# LaserDriver.net
KiCad netlist of a schematic drawn in Altium Designer
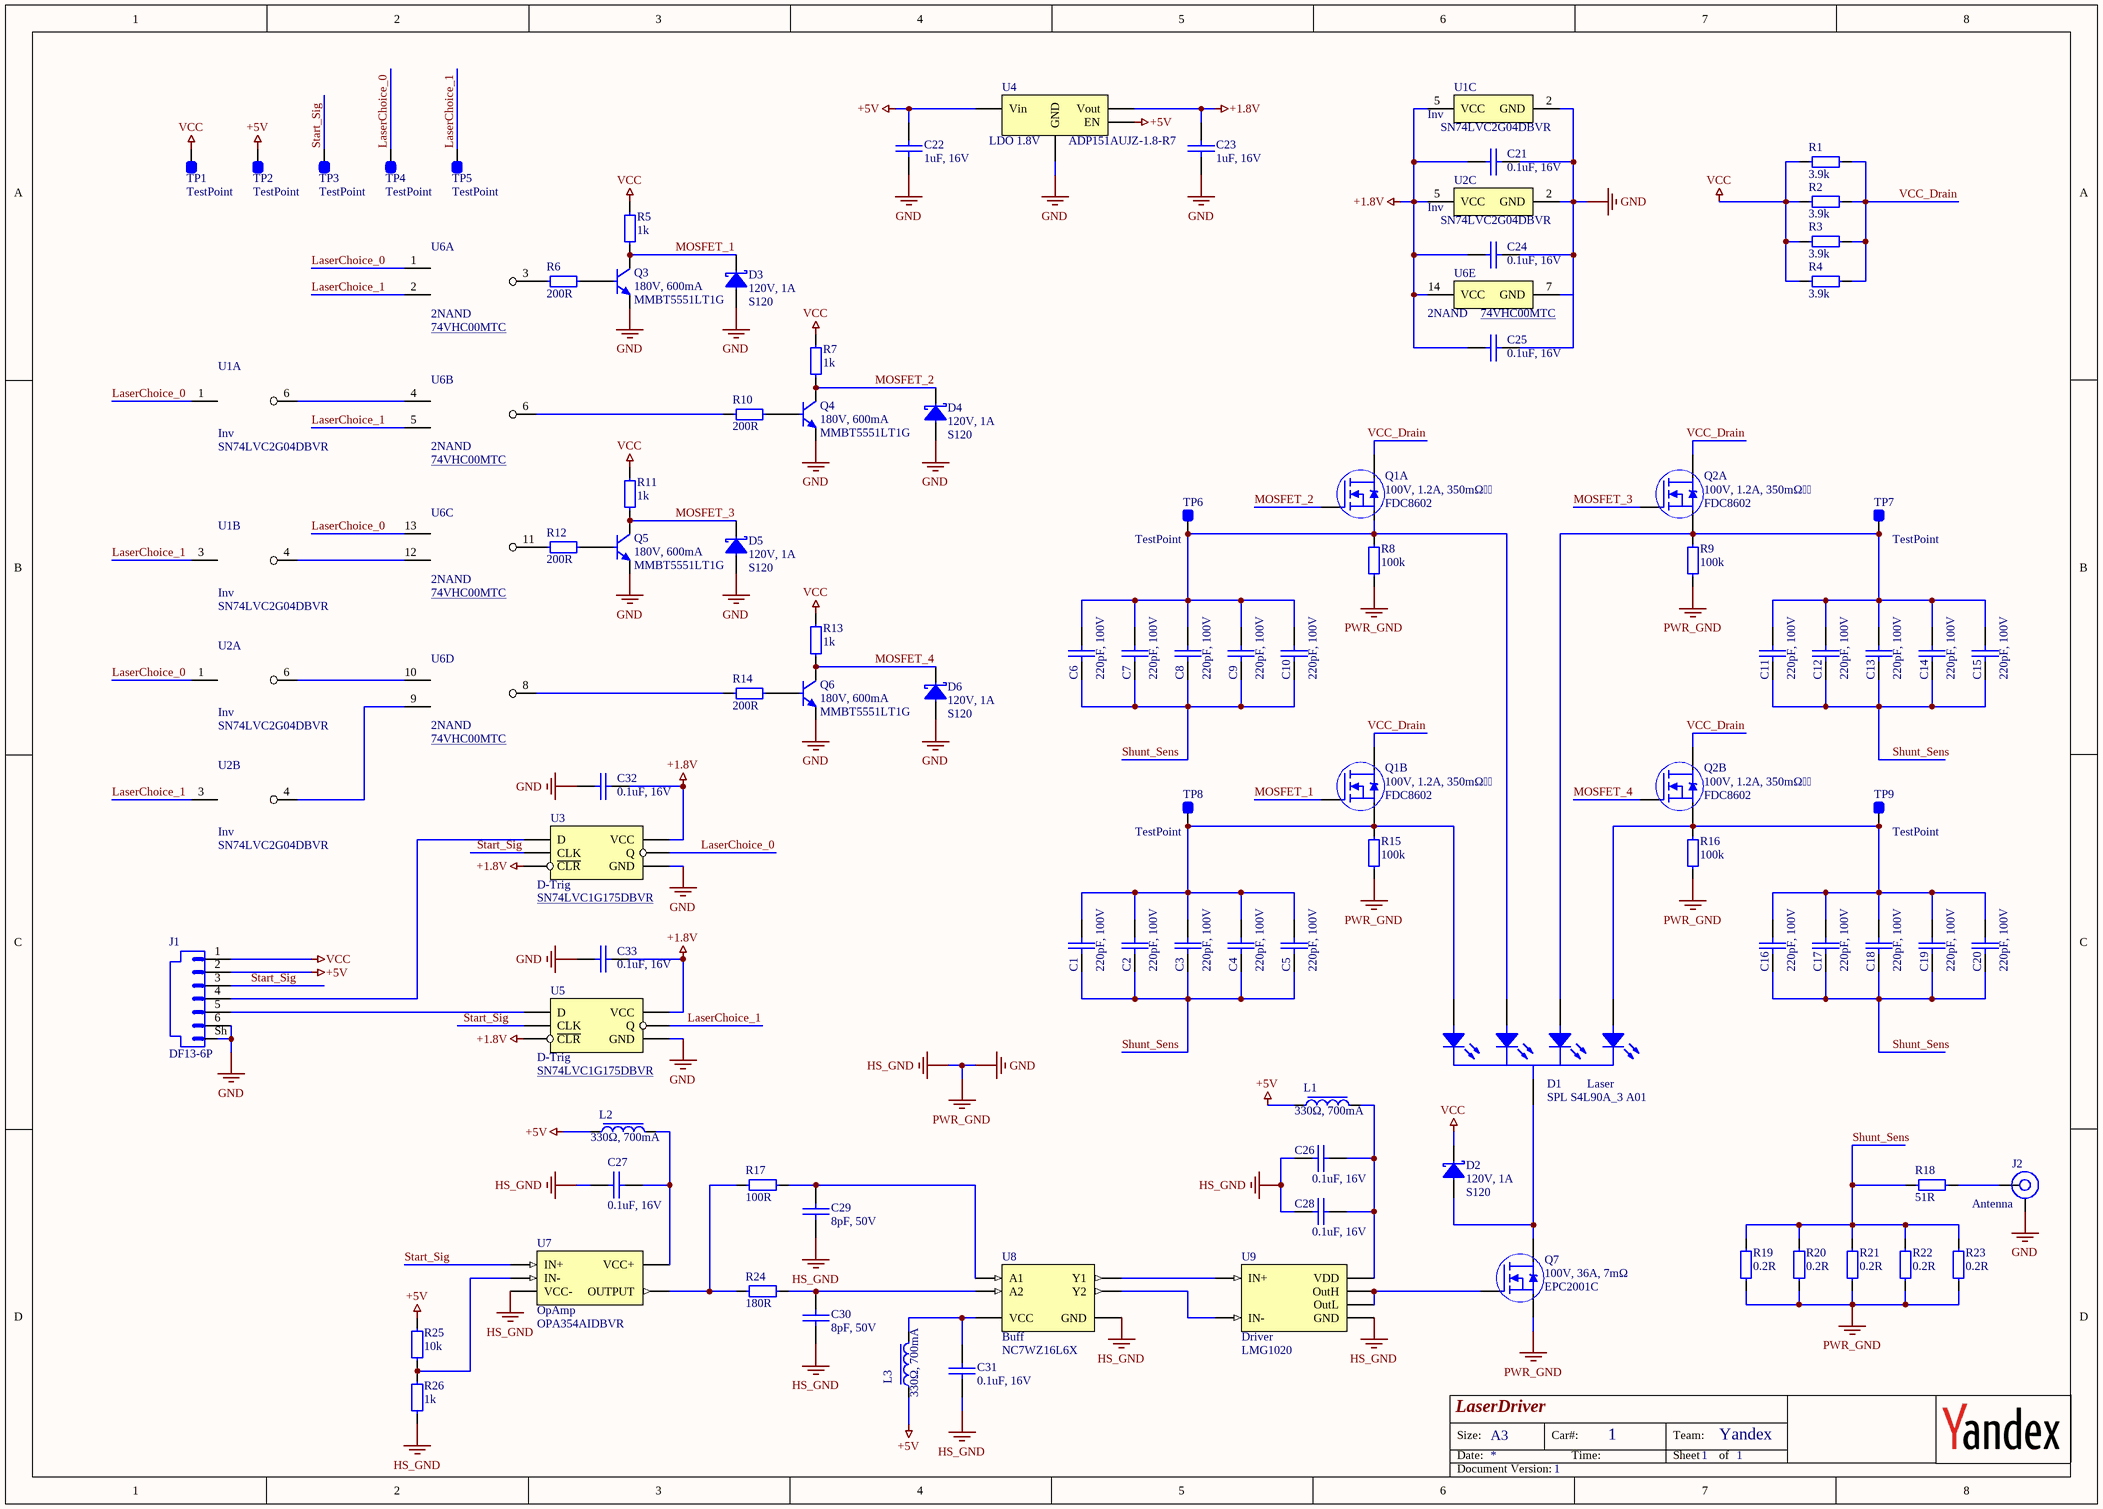
[diagram p0: LaserDriver.SchDoc]

(export (version "E")
  (design (tool "Eeschema 10.0.6"))
  (components
    (comp (ref "C1")
      (value "220pF, 100V")
      (footprint "0402 Capicator")
      (description "NP0 220pF 100V 5% 0402")
      (fields (field (name "MANUFACTURER") "TDK") (field (name "PART NUMBER") "C1005C0G2A221J050BA"))
      (libsource (lib "BRT_Components") (part "Cap 220pF (0402)"))
    )
    (comp (ref "C2")
      (value "220pF, 100V")
      (footprint "0402 Capicator")
      (description "NP0 220pF 100V 5% 0402")
      (fields (field (name "MANUFACTURER") "TDK") (field (name "PART NUMBER") "C1005C0G2A221J050BA"))
      (libsource (lib "BRT_Components") (part "Cap 220pF (0402)"))
    )
    (comp (ref "C3")
      (value "220pF, 100V")
      (footprint "0402 Capicator")
      (description "NP0 220pF 100V 5% 0402")
      (fields (field (name "MANUFACTURER") "TDK") (field (name "PART NUMBER") "C1005C0G2A221J050BA"))
      (libsource (lib "BRT_Components") (part "Cap 220pF (0402)"))
    )
    (comp (ref "C4")
      (value "220pF, 100V")
      (footprint "0402 Capicator")
      (description "NP0 220pF 100V 5% 0402")
      (fields (field (name "MANUFACTURER") "TDK") (field (name "PART NUMBER") "C1005C0G2A221J050BA"))
      (libsource (lib "BRT_Components") (part "Cap 220pF (0402)"))
    )
    (comp (ref "C5")
      (value "220pF, 100V")
      (footprint "0402 Capicator")
      (description "NP0 220pF 100V 5% 0402")
      (fields (field (name "MANUFACTURER") "TDK") (field (name "PART NUMBER") "C1005C0G2A221J050BA"))
      (libsource (lib "BRT_Components") (part "Cap 220pF (0402)"))
    )
    (comp (ref "C6")
      (value "220pF, 100V")
      (footprint "0402 Capicator")
      (description "NP0 220pF 100V 5% 0402")
      (fields (field (name "MANUFACTURER") "TDK") (field (name "PART NUMBER") "C1005C0G2A221J050BA"))
      (libsource (lib "BRT_Components") (part "Cap 220pF (0402)"))
    )
    (comp (ref "C7")
      (value "220pF, 100V")
      (footprint "0402 Capicator")
      (description "NP0 220pF 100V 5% 0402")
      (fields (field (name "MANUFACTURER") "TDK") (field (name "PART NUMBER") "C1005C0G2A221J050BA"))
      (libsource (lib "BRT_Components") (part "Cap 220pF (0402)"))
    )
    (comp (ref "C8")
      (value "220pF, 100V")
      (footprint "0402 Capicator")
      (description "NP0 220pF 100V 5% 0402")
      (fields (field (name "MANUFACTURER") "TDK") (field (name "PART NUMBER") "C1005C0G2A221J050BA"))
      (libsource (lib "BRT_Components") (part "Cap 220pF (0402)"))
    )
    (comp (ref "C9")
      (value "220pF, 100V")
      (footprint "0402 Capicator")
      (description "NP0 220pF 100V 5% 0402")
      (fields (field (name "MANUFACTURER") "TDK") (field (name "PART NUMBER") "C1005C0G2A221J050BA"))
      (libsource (lib "BRT_Components") (part "Cap 220pF (0402)"))
    )
    (comp (ref "C10")
      (value "220pF, 100V")
      (footprint "0402 Capicator")
      (description "NP0 220pF 100V 5% 0402")
      (fields (field (name "MANUFACTURER") "TDK") (field (name "PART NUMBER") "C1005C0G2A221J050BA"))
      (libsource (lib "BRT_Components") (part "Cap 220pF (0402)"))
    )
    (comp (ref "C11")
      (value "220pF, 100V")
      (footprint "0402 Capicator")
      (description "NP0 220pF 100V 5% 0402")
      (fields (field (name "MANUFACTURER") "TDK") (field (name "PART NUMBER") "C1005C0G2A221J050BA"))
      (libsource (lib "BRT_Components") (part "Cap 220pF (0402)"))
    )
    (comp (ref "C12")
      (value "220pF, 100V")
      (footprint "0402 Capicator")
      (description "NP0 220pF 100V 5% 0402")
      (fields (field (name "MANUFACTURER") "TDK") (field (name "PART NUMBER") "C1005C0G2A221J050BA"))
      (libsource (lib "BRT_Components") (part "Cap 220pF (0402)"))
    )
    (comp (ref "C13")
      (value "220pF, 100V")
      (footprint "0402 Capicator")
      (description "NP0 220pF 100V 5% 0402")
      (fields (field (name "MANUFACTURER") "TDK") (field (name "PART NUMBER") "C1005C0G2A221J050BA"))
      (libsource (lib "BRT_Components") (part "Cap 220pF (0402)"))
    )
    (comp (ref "C14")
      (value "220pF, 100V")
      (footprint "0402 Capicator")
      (description "NP0 220pF 100V 5% 0402")
      (fields (field (name "MANUFACTURER") "TDK") (field (name "PART NUMBER") "C1005C0G2A221J050BA"))
      (libsource (lib "BRT_Components") (part "Cap 220pF (0402)"))
    )
    (comp (ref "C15")
      (value "220pF, 100V")
      (footprint "0402 Capicator")
      (description "NP0 220pF 100V 5% 0402")
      (fields (field (name "MANUFACTURER") "TDK") (field (name "PART NUMBER") "C1005C0G2A221J050BA"))
      (libsource (lib "BRT_Components") (part "Cap 220pF (0402)"))
    )
    (comp (ref "C16")
      (value "220pF, 100V")
      (footprint "0402 Capicator")
      (description "NP0 220pF 100V 5% 0402")
      (fields (field (name "MANUFACTURER") "TDK") (field (name "PART NUMBER") "C1005C0G2A221J050BA"))
      (libsource (lib "BRT_Components") (part "Cap 220pF (0402)"))
    )
    (comp (ref "C17")
      (value "220pF, 100V")
      (footprint "0402 Capicator")
      (description "NP0 220pF 100V 5% 0402")
      (fields (field (name "MANUFACTURER") "TDK") (field (name "PART NUMBER") "C1005C0G2A221J050BA"))
      (libsource (lib "BRT_Components") (part "Cap 220pF (0402)"))
    )
    (comp (ref "C18")
      (value "220pF, 100V")
      (footprint "0402 Capicator")
      (description "NP0 220pF 100V 5% 0402")
      (fields (field (name "MANUFACTURER") "TDK") (field (name "PART NUMBER") "C1005C0G2A221J050BA"))
      (libsource (lib "BRT_Components") (part "Cap 220pF (0402)"))
    )
    (comp (ref "C19")
      (value "220pF, 100V")
      (footprint "0402 Capicator")
      (description "NP0 220pF 100V 5% 0402")
      (fields (field (name "MANUFACTURER") "TDK") (field (name "PART NUMBER") "C1005C0G2A221J050BA"))
      (libsource (lib "BRT_Components") (part "Cap 220pF (0402)"))
    )
    (comp (ref "C20")
      (value "220pF, 100V")
      (footprint "0402 Capicator")
      (description "NP0 220pF 100V 5% 0402")
      (fields (field (name "MANUFACTURER") "TDK") (field (name "PART NUMBER") "C1005C0G2A221J050BA"))
      (libsource (lib "BRT_Components") (part "Cap 220pF (0402)"))
    )
    (comp (ref "C21")
      (value "0.1uF, 16V")
      (footprint "0402 Capicator")
      (description "X7R 0.1uF 16V 10% 0402")
      (fields
        (field (name "MANUFACTURER") "Murata Electronics")
        (field (name "PART NUMBER") "GRM155R71C104KA88B")
      )
      (libsource (lib "BRT_Components") (part "Cap 0.1uF (0402)"))
    )
    (comp (ref "C22")
      (value "1uF, 16V")
      (footprint "0402 Capicator")
      (description "X5R 0.1uF 16V 10% 0402")
      (fields
        (field (name "MANUFACTURER") "Murata Electronics")
        (field (name "PART NUMBER") "GRM155R61C105KA12D")
      )
      (libsource (lib "BRT_Components") (part "Cap 1uF (0402)"))
    )
    (comp (ref "C23")
      (value "1uF, 16V")
      (footprint "0402 Capicator")
      (description "X5R 0.1uF 16V 10% 0402")
      (fields
        (field (name "MANUFACTURER") "Murata Electronics")
        (field (name "PART NUMBER") "GRM155R61C105KA12D")
      )
      (libsource (lib "BRT_Components") (part "Cap 1uF (0402)"))
    )
    (comp (ref "C24")
      (value "0.1uF, 16V")
      (footprint "0402 Capicator")
      (description "X7R 0.1uF 16V 10% 0402")
      (fields
        (field (name "MANUFACTURER") "Murata Electronics")
        (field (name "PART NUMBER") "GRM155R71C104KA88B")
      )
      (libsource (lib "BRT_Components") (part "Cap 0.1uF (0402)"))
    )
    (comp (ref "C25")
      (value "0.1uF, 16V")
      (footprint "0402 Capicator")
      (description "X7R 0.1uF 16V 10% 0402")
      (fields
        (field (name "MANUFACTURER") "Murata Electronics")
        (field (name "PART NUMBER") "GRM155R71C104KA88B")
      )
      (libsource (lib "BRT_Components") (part "Cap 0.1uF (0402)"))
    )
    (comp (ref "C26")
      (value "0.1uF, 16V")
      (footprint "0402 Capicator")
      (description "X7R 0.1uF 16V 10% 0402")
      (fields
        (field (name "MANUFACTURER") "Murata Electronics")
        (field (name "PART NUMBER") "GRM155R71C104KA88B")
      )
      (libsource (lib "BRT_Components") (part "Cap 0.1uF (0402)"))
    )
    (comp (ref "C27")
      (value "0.1uF, 16V")
      (footprint "0402 Capicator")
      (description "X7R 0.1uF 16V 10% 0402")
      (fields
        (field (name "MANUFACTURER") "Murata Electronics")
        (field (name "PART NUMBER") "GRM155R71C104KA88B")
      )
      (libsource (lib "BRT_Components") (part "Cap 0.1uF (0402)"))
    )
    (comp (ref "C28")
      (value "0.1uF, 16V")
      (footprint "0402 Capicator")
      (description "X7R 0.1uF 16V 10% 0402")
      (fields
        (field (name "MANUFACTURER") "Murata Electronics")
        (field (name "PART NUMBER") "GRM155R71C104KA88B")
      )
      (libsource (lib "BRT_Components") (part "Cap 0.1uF (0402)"))
    )
    (comp (ref "C29")
      (value "8pF, 50V")
      (footprint "0603 Capicator")
      (description "8pF±0.1pF NP0 50V 0603")
      (fields
        (field (name "MANUFACTURER") "Murata Electronics")
        (field (name "PART NUMBER") "GRM1885C1H8R0BA01D")
      )
      (libsource (lib "BRT_Components") (part "Cap 8pF (0603)"))
    )
    (comp (ref "C30")
      (value "8pF, 50V")
      (footprint "0603 Capicator")
      (description "8pF±0.1pF NP0 50V 0603")
      (fields
        (field (name "MANUFACTURER") "Murata Electronics")
        (field (name "PART NUMBER") "GRM1885C1H8R0BA01D")
      )
      (libsource (lib "BRT_Components") (part "Cap 8pF (0603)"))
    )
    (comp (ref "C31")
      (value "0.1uF, 16V")
      (footprint "0402 Capicator")
      (description "X7R 0.1uF 16V 10% 0402")
      (fields
        (field (name "MANUFACTURER") "Murata Electronics")
        (field (name "PART NUMBER") "GRM155R71C104KA88B")
      )
      (libsource (lib "BRT_Components") (part "Cap 0.1uF (0402)"))
    )
    (comp (ref "C32")
      (value "0.1uF, 16V")
      (footprint "0402 Capicator")
      (description "X7R 0.1uF 16V 10% 0402")
      (fields
        (field (name "MANUFACTURER") "Murata Electronics")
        (field (name "PART NUMBER") "GRM155R71C104KA88B")
      )
      (libsource (lib "BRT_Components") (part "Cap 0.1uF (0402)"))
    )
    (comp (ref "C33")
      (value "0.1uF, 16V")
      (footprint "0402 Capicator")
      (description "X7R 0.1uF 16V 10% 0402")
      (fields
        (field (name "MANUFACTURER") "Murata Electronics")
        (field (name "PART NUMBER") "GRM155R71C104KA88B")
      )
      (libsource (lib "BRT_Components") (part "Cap 0.1uF (0402)"))
    )
    (comp (ref "D1")
      (value "Laser")
      (footprint "SPL S4L90A_3 A01")
      (description "4 Channel SMT Laser in QFN package")
      (fields
        (field (name "MANUFACTURER") "OSRAM Opto Semiconductors")
        (field (name "PART NUMBER") "SPL S4L90A_3 A01")
      )
      (libsource (lib "BRT_Components") (part "Laser 4 Channel"))
    )
    (comp (ref "D2")
      (value "120V, 1A")
      (footprint "SOD-123FL")
      (fields
        (field (name "MANUFACTURER") "Yangzhou Yangjie Electronic Technology Co")
        (field (name "PART NUMBER") "S120")
      )
      (libsource (lib "BRT_Components") (part "Diode Schottky (SOD-123FL)"))
    )
    (comp (ref "D3")
      (value "120V, 1A")
      (footprint "SOD-123FL")
      (fields
        (field (name "MANUFACTURER") "Yangzhou Yangjie Electronic Technology Co")
        (field (name "PART NUMBER") "S120")
      )
      (libsource (lib "BRT_Components") (part "Diode Schottky (SOD-123FL)"))
    )
    (comp (ref "D4")
      (value "120V, 1A")
      (footprint "SOD-123FL")
      (fields
        (field (name "MANUFACTURER") "Yangzhou Yangjie Electronic Technology Co")
        (field (name "PART NUMBER") "S120")
      )
      (libsource (lib "BRT_Components") (part "Diode Schottky (SOD-123FL)"))
    )
    (comp (ref "D5")
      (value "120V, 1A")
      (footprint "SOD-123FL")
      (fields
        (field (name "MANUFACTURER") "Yangzhou Yangjie Electronic Technology Co")
        (field (name "PART NUMBER") "S120")
      )
      (libsource (lib "BRT_Components") (part "Diode Schottky (SOD-123FL)"))
    )
    (comp (ref "D6")
      (value "120V, 1A")
      (footprint "SOD-123FL")
      (fields
        (field (name "MANUFACTURER") "Yangzhou Yangjie Electronic Technology Co")
        (field (name "PART NUMBER") "S120")
      )
      (libsource (lib "BRT_Components") (part "Diode Schottky (SOD-123FL)"))
    )
    (comp (ref "J1")
      (value "DF13-6P")
      (footprint "DF13-6p-1.25H")
      (description "[DF13-6P-1.25H]")
      (fields (field (name "MANUFACTURER") "Hirose") (field (name "PART NUMBER") "CL0536-0255-2-75"))
      (libsource (lib "BRT_Components") (part "Conn 6 [DF13]"))
    )
    (comp (ref "J2")
      (value "Antenna")
      (footprint "IPX U. FL")
      (description "[IPX U. FL]")
      (fields (field (name "PART NUMBER") "IPX U. FL") (field (name "MANUFACTURER") "DIY BOX"))
      (libsource (lib "BRT_Components") (part "Connector SMT"))
    )
    (comp (ref "L1")
      (value "330Ω, 700mA")
      (footprint "0402 Inductor")
      (description "Chip beads for power line. GHz noise countermeasure")
      (fields (field (name "PART NUMBER") "MPZ1005S331ET000") (field (name "MANUFACTURER") "TDK"))
      (libsource (lib "BRT_Components") (part "Ferrite Bead 330 (0402)"))
    )
    (comp (ref "L2")
      (value "330Ω, 700mA")
      (footprint "0402 Inductor")
      (description "Chip beads for power line. GHz noise countermeasure")
      (fields (field (name "PART NUMBER") "MPZ1005S331ET000") (field (name "MANUFACTURER") "TDK"))
      (libsource (lib "BRT_Components") (part "Ferrite Bead 330 (0402)"))
    )
    (comp (ref "L3")
      (value "330Ω, 700mA")
      (footprint "0402 Inductor")
      (description "Chip beads for power line. GHz noise countermeasure")
      (fields (field (name "PART NUMBER") "MPZ1005S331ET000") (field (name "MANUFACTURER") "TDK"))
      (libsource (lib "BRT_Components") (part "Ferrite Bead 330 (0402)"))
    )
    (comp (ref "Q1")
      (value "100V, 1.2A, 350mΩ")
      (footprint "SOT236")
      (description "Dual N-Channel Shielded Gate PowerTrench")
      (fields (field (name "MANUFACTURER") "Onsemi") (field (name "PART NUMBER") "FDC8602"))
      (libsource (lib "BRT_Components") (part "MOSFET-N x2 [FDC86]"))
    )
    (comp (ref "Q2")
      (value "100V, 1.2A, 350mΩ")
      (footprint "SOT236")
      (description "Dual N-Channel Shielded Gate PowerTrench")
      (fields (field (name "MANUFACTURER") "Onsemi") (field (name "PART NUMBER") "FDC8602"))
      (libsource (lib "BRT_Components") (part "MOSFET-N x2 [FDC86]"))
    )
    (comp (ref "Q3")
      (value "180V, 600mA")
      (footprint "SOT-23")
      (description "NPN high voltage transistor. AEC−Q101 Qualified and PPAP Capable.")
      (fields (field (name "MANUFACTURER") "ON Semiconductor") (field (name "PART NUMBER") "MMBT5551LT1G"))
      (libsource (lib "BRT_Components") (part "NPN [MMBT]"))
    )
    (comp (ref "Q4")
      (value "180V, 600mA")
      (footprint "SOT-23")
      (description "NPN high voltage transistor. AEC−Q101 Qualified and PPAP Capable.")
      (fields (field (name "MANUFACTURER") "ON Semiconductor") (field (name "PART NUMBER") "MMBT5551LT1G"))
      (libsource (lib "BRT_Components") (part "NPN [MMBT]"))
    )
    (comp (ref "Q5")
      (value "180V, 600mA")
      (footprint "SOT-23")
      (description "NPN high voltage transistor. AEC−Q101 Qualified and PPAP Capable.")
      (fields (field (name "MANUFACTURER") "ON Semiconductor") (field (name "PART NUMBER") "MMBT5551LT1G"))
      (libsource (lib "BRT_Components") (part "NPN [MMBT]"))
    )
    (comp (ref "Q6")
      (value "180V, 600mA")
      (footprint "SOT-23")
      (description "NPN high voltage transistor. AEC−Q101 Qualified and PPAP Capable.")
      (fields (field (name "MANUFACTURER") "ON Semiconductor") (field (name "PART NUMBER") "MMBT5551LT1G"))
      (libsource (lib "BRT_Components") (part "NPN [MMBT]"))
    )
    (comp (ref "Q7")
      (value "100V, 36A, 7mΩ")
      (footprint "EPC2001C")
      (description "eGaN FET")
      (fields (field (name "MANUFACTURER") "EPC") (field (name "PART NUMBER") "EPC2001C"))
      (libsource (lib "BRT_Components") (part "MOSFET-N [EPC]"))
    )
    (comp (ref "R1")
      (value "3.9k")
      (footprint "0402 Resistor")
      (description "0.062W 0403 3.9k 1%")
      (fields (field (name "PART NUMBER") "RC0402FR-073K9L") (field (name "MANUFACTURER") "Taiwan"))
      (libsource (lib "BRT_Components") (part "Res 3.9k (0402)"))
    )
    (comp (ref "R2")
      (value "3.9k")
      (footprint "0402 Resistor")
      (description "0.062W 0403 3.9k 1%")
      (fields (field (name "PART NUMBER") "RC0402FR-073K9L") (field (name "MANUFACTURER") "Taiwan"))
      (libsource (lib "BRT_Components") (part "Res 3.9k (0402)"))
    )
    (comp (ref "R3")
      (value "3.9k")
      (footprint "0402 Resistor")
      (description "0.062W 0403 3.9k 1%")
      (fields (field (name "PART NUMBER") "RC0402FR-073K9L") (field (name "MANUFACTURER") "Taiwan"))
      (libsource (lib "BRT_Components") (part "Res 3.9k (0402)"))
    )
    (comp (ref "R4")
      (value "3.9k")
      (footprint "0402 Resistor")
      (description "0.062W 0403 3.9k 1%")
      (fields (field (name "PART NUMBER") "RC0402FR-073K9L") (field (name "MANUFACTURER") "Taiwan"))
      (libsource (lib "BRT_Components") (part "Res 3.9k (0402)"))
    )
    (comp (ref "R5")
      (value "1k")
      (footprint "0402 Resistor")
      (description "0.062W 0403 1k 1%")
      (fields (field (name "PART NUMBER") "RC0402FR-071KL") (field (name "MANUFACTURER") "Taiwan"))
      (libsource (lib "BRT_Components") (part "Res 1k (0402)"))
    )
    (comp (ref "R6")
      (value "200R")
      (footprint "0402 Resistor")
      (description "0.062W 0403 200R 1%")
      (fields (field (name "PART NUMBER") "RC0402FR-07200RL") (field (name "MANUFACTURER") "Taiwan"))
      (libsource (lib "BRT_Components") (part "Res 200R (0402)"))
    )
    (comp (ref "R7")
      (value "1k")
      (footprint "0402 Resistor")
      (description "0.062W 0403 1k 1%")
      (fields (field (name "PART NUMBER") "RC0402FR-071KL") (field (name "MANUFACTURER") "Taiwan"))
      (libsource (lib "BRT_Components") (part "Res 1k (0402)"))
    )
    (comp (ref "R8")
      (value "100k")
      (footprint "0402 Resistor")
      (description "0.062W 0403 100k 1%")
      (fields (field (name "PART NUMBER") "RC0402FR-07100KL") (field (name "MANUFACTURER") "Taiwan"))
      (libsource (lib "BRT_Components") (part "Res 100k (0402)"))
    )
    (comp (ref "R9")
      (value "100k")
      (footprint "0402 Resistor")
      (description "0.062W 0403 100k 1%")
      (fields (field (name "PART NUMBER") "RC0402FR-07100KL") (field (name "MANUFACTURER") "Taiwan"))
      (libsource (lib "BRT_Components") (part "Res 100k (0402)"))
    )
    (comp (ref "R10")
      (value "200R")
      (footprint "0402 Resistor")
      (description "0.062W 0403 200R 1%")
      (fields (field (name "PART NUMBER") "RC0402FR-07200RL") (field (name "MANUFACTURER") "Taiwan"))
      (libsource (lib "BRT_Components") (part "Res 200R (0402)"))
    )
    (comp (ref "R11")
      (value "1k")
      (footprint "0402 Resistor")
      (description "0.062W 0403 1k 1%")
      (fields (field (name "PART NUMBER") "RC0402FR-071KL") (field (name "MANUFACTURER") "Taiwan"))
      (libsource (lib "BRT_Components") (part "Res 1k (0402)"))
    )
    (comp (ref "R12")
      (value "200R")
      (footprint "0402 Resistor")
      (description "0.062W 0403 200R 1%")
      (fields (field (name "PART NUMBER") "RC0402FR-07200RL") (field (name "MANUFACTURER") "Taiwan"))
      (libsource (lib "BRT_Components") (part "Res 200R (0402)"))
    )
    (comp (ref "R13")
      (value "1k")
      (footprint "0402 Resistor")
      (description "0.062W 0403 1k 1%")
      (fields (field (name "PART NUMBER") "RC0402FR-071KL") (field (name "MANUFACTURER") "Taiwan"))
      (libsource (lib "BRT_Components") (part "Res 1k (0402)"))
    )
    (comp (ref "R14")
      (value "200R")
      (footprint "0402 Resistor")
      (description "0.062W 0403 200R 1%")
      (fields (field (name "PART NUMBER") "RC0402FR-07200RL") (field (name "MANUFACTURER") "Taiwan"))
      (libsource (lib "BRT_Components") (part "Res 200R (0402)"))
    )
    (comp (ref "R15")
      (value "100k")
      (footprint "0402 Resistor")
      (description "0.062W 0403 100k 1%")
      (fields (field (name "PART NUMBER") "RC0402FR-07100KL") (field (name "MANUFACTURER") "Taiwan"))
      (libsource (lib "BRT_Components") (part "Res 100k (0402)"))
    )
    (comp (ref "R16")
      (value "100k")
      (footprint "0402 Resistor")
      (description "0.062W 0403 100k 1%")
      (fields (field (name "PART NUMBER") "RC0402FR-07100KL") (field (name "MANUFACTURER") "Taiwan"))
      (libsource (lib "BRT_Components") (part "Res 100k (0402)"))
    )
    (comp (ref "R17")
      (value "100R")
      (footprint "0402 Resistor")
      (description "0.062W 0403 100R, 1%")
      (fields (field (name "PART NUMBER") "RC0402JR-07100RL") (field (name "MANUFACTURER") "Taiwan"))
      (libsource (lib "BRT_Components") (part "Res 100R (0402)"))
    )
    (comp (ref "R18")
      (value "51R")
      (footprint "0402 Resistor")
      (description "0.062W 0403 51R 1%")
      (fields (field (name "PART NUMBER") "RC0402FR-0751RL") (field (name "MANUFACTURER") "Taiwan"))
      (libsource (lib "BRT_Components") (part "Res 51R (0402)"))
    )
    (comp (ref "R19")
      (value "0.2R")
      (footprint "0402 Resistor")
      (description "0.125W 0402 0.2R, 1%")
      (fields (field (name "PART NUMBER") "UCR01MVPFLR200") (field (name "MANUFACTURER") "Rohm"))
      (libsource (lib "BRT_Components") (part "Res 0.2R (0402)"))
    )
    (comp (ref "R20")
      (value "0.2R")
      (footprint "0402 Resistor")
      (description "0.125W 0402 0.2R, 1%")
      (fields (field (name "PART NUMBER") "UCR01MVPFLR200") (field (name "MANUFACTURER") "Rohm"))
      (libsource (lib "BRT_Components") (part "Res 0.2R (0402)"))
    )
    (comp (ref "R21")
      (value "0.2R")
      (footprint "0402 Resistor")
      (description "0.125W 0402 0.2R, 1%")
      (fields (field (name "PART NUMBER") "UCR01MVPFLR200") (field (name "MANUFACTURER") "Rohm"))
      (libsource (lib "BRT_Components") (part "Res 0.2R (0402)"))
    )
    (comp (ref "R22")
      (value "0.2R")
      (footprint "0402 Resistor")
      (description "0.125W 0402 0.2R, 1%")
      (fields (field (name "PART NUMBER") "UCR01MVPFLR200") (field (name "MANUFACTURER") "Rohm"))
      (libsource (lib "BRT_Components") (part "Res 0.2R (0402)"))
    )
    (comp (ref "R23")
      (value "0.2R")
      (footprint "0402 Resistor")
      (description "0.125W 0402 0.2R, 1%")
      (fields (field (name "PART NUMBER") "UCR01MVPFLR200") (field (name "MANUFACTURER") "Rohm"))
      (libsource (lib "BRT_Components") (part "Res 0.2R (0402)"))
    )
    (comp (ref "R24")
      (value "180R")
      (footprint "0402 Resistor")
      (description "0.062W 0403 180R, 1%")
      (fields (field (name "PART NUMBER") "RC0402FR-07180RL") (field (name "MANUFACTURER") "Taiwan"))
      (libsource (lib "BRT_Components") (part "Res 180R (0402)"))
    )
    (comp (ref "R25")
      (value "10k")
      (footprint "0402 Resistor")
      (description "0.062W 0403 10k 1%")
      (fields (field (name "PART NUMBER") "RC0402FR-0710KL") (field (name "MANUFACTURER") "Taiwan"))
      (libsource (lib "BRT_Components") (part "Res 10k (0402)"))
    )
    (comp (ref "R26")
      (value "1k")
      (footprint "0402 Resistor")
      (description "0.062W 0403 1k 1%")
      (fields (field (name "PART NUMBER") "RC0402FR-071KL") (field (name "MANUFACTURER") "Taiwan"))
      (libsource (lib "BRT_Components") (part "Res 1k (0402)"))
    )
    (comp (ref "TP1")
      (value "TestPoint")
      (footprint "TestPoint")
      (libsource (lib "BRT_Components") (part "TestPoint"))
    )
    (comp (ref "TP2")
      (value "TestPoint")
      (footprint "TestPoint")
      (libsource (lib "BRT_Components") (part "TestPoint"))
    )
    (comp (ref "TP3")
      (value "TestPoint")
      (footprint "TestPoint")
      (libsource (lib "BRT_Components") (part "TestPoint"))
    )
    (comp (ref "TP4")
      (value "TestPoint")
      (footprint "TestPoint")
      (libsource (lib "BRT_Components") (part "TestPoint"))
    )
    (comp (ref "TP5")
      (value "TestPoint")
      (footprint "TestPoint")
      (libsource (lib "BRT_Components") (part "TestPoint"))
    )
    (comp (ref "TP6")
      (value "TestPoint")
      (footprint "TestPoint")
      (libsource (lib "BRT_Components") (part "TestPoint"))
    )
    (comp (ref "TP7")
      (value "TestPoint")
      (footprint "TestPoint")
      (libsource (lib "BRT_Components") (part "TestPoint"))
    )
    (comp (ref "TP8")
      (value "TestPoint")
      (footprint "TestPoint")
      (libsource (lib "BRT_Components") (part "TestPoint"))
    )
    (comp (ref "TP9")
      (value "TestPoint")
      (footprint "TestPoint")
      (libsource (lib "BRT_Components") (part "TestPoint"))
    )
    (comp (ref "U1")
      (value "Inv")
      (footprint "SOT236")
      (description "Dual inverter, 1.65-5.5V")
      (fields
        (field (name "MANUFACTURER") "Texas Instruments")
        (field (name "PART NUMBER") "SN74LVC2G04DBVR")
      )
      (libsource (lib "BRT_Components") (part "Inverter (SN74)"))
    )
    (comp (ref "U2")
      (value "Inv")
      (footprint "SOT236")
      (description "Dual inverter, 1.65-5.5V")
      (fields
        (field (name "MANUFACTURER") "Texas Instruments")
        (field (name "PART NUMBER") "SN74LVC2G04DBVR")
      )
      (libsource (lib "BRT_Components") (part "Inverter (SN74)"))
    )
    (comp (ref "U3")
      (value "D-Trig")
      (footprint "SOT236")
      (description "The single D-type flip-flop designed for 1.65-V to 5.5-V VCC operation")
      (fields
        (field (name "MANUFACTURER") "Texas Instruments")
        (field (name "PART NUMBER") "SN74LVC1G175DBVR")
      )
      (libsource (lib "BRT_Components") (part "D-Trigger [SN74LVC1G175DBVR]"))
    )
    (comp (ref "U4")
      (value "LDO 1.8V")
      (footprint "SOT-23-5")
      (fields (field (name "MANUFACTURER") "Analog Devices") (field (name "PART NUMBER") "ADP151AUJZ-1.8-R7"))
      (libsource (lib "BRT_Components") (part "LDO 1.8V [ADP]"))
    )
    (comp (ref "U5")
      (value "D-Trig")
      (footprint "SOT236")
      (description "The single D-type flip-flop designed for 1.65-V to 5.5-V VCC operation")
      (fields
        (field (name "MANUFACTURER") "Texas Instruments")
        (field (name "PART NUMBER") "SN74LVC1G175DBVR")
      )
      (libsource (lib "BRT_Components") (part "D-Trigger [SN74LVC1G175DBVR]"))
    )
    (comp (ref "U6")
      (value "2NAND")
      (footprint "TSSOP-14")
      (description "4 logic elements \"2NAND\"")
      (fields
        (field (name "MANUFACTURER") "Fairchild Semiconductor")
        (field (name "PART NUMBER") "74VHC00MTC")
      )
      (libsource (lib "BRT_Components") (part "4(2NAND) 1.5V Logic"))
    )
    (comp (ref "U7")
      (value "OpAmp")
      (footprint "SOT-23-5")
      (fields (field (name "MANUFACTURER") "Texas Instruments") (field (name "PART NUMBER") "OPA354AIDBVR"))
      (libsource (lib "BRT_Components") (part "OpAmp [OPA354]"))
    )
    (comp (ref "U8")
      (value "Buff")
      (footprint "MicroPak 6-Lead")
      (fields (field (name "MANUFACTURER") "Onsemi") (field (name "PART NUMBER") "NC7WZ16L6X"))
      (libsource (lib "BRT_Components") (part "Buffer [NC7]"))
    )
    (comp (ref "U9")
      (value "Driver")
      (footprint "WCSP")
      (fields (field (name "MANUFACTURER") "Texas Instruments") (field (name "PART NUMBER") "LMG1020"))
      (libsource (lib "BRT_Components") (part "MOSFET Driver [LMG]"))
    )
  )
  (nets
    (net (code "1") (name "+1.8V") (class "Default")
      (node (ref "C21") (pin "1") (pinfunction "1_1") (pintype "passive"))
      (node (ref "C23") (pin "2") (pinfunction "2_2") (pintype "passive"))
      (node (ref "C24") (pin "1") (pinfunction "1_1") (pintype "passive"))
      (node (ref "C25") (pin "1") (pinfunction "1_1") (pintype "passive"))
      (node (ref "C32") (pin "2") (pinfunction "2_2") (pintype "passive"))
      (node (ref "C33") (pin "2") (pinfunction "2_2") (pintype "passive"))
      (node (ref "U1") (pin "5") (pinfunction "VCC_5") (pintype "power_in"))
      (node (ref "U2") (pin "5") (pinfunction "VCC_5") (pintype "power_in"))
      (node (ref "U3") (pin "5") (pinfunction "VCC_5") (pintype "power_in"))
      (node (ref "U3") (pin "6") (pinfunction "~{CLR}_6") (pintype "passive"))
      (node (ref "U4") (pin "5") (pinfunction "Vout_5") (pintype "power_in"))
      (node (ref "U5") (pin "5") (pinfunction "VCC_5") (pintype "power_in"))
      (node (ref "U5") (pin "6") (pinfunction "~{CLR}_6") (pintype "passive"))
      (node (ref "U6") (pin "14") (pinfunction "VCC_14") (pintype "power_in"))
    )
    (net (code "2") (name "+5V") (class "Default")
      (node (ref "C22") (pin "2") (pinfunction "2_2") (pintype "passive"))
      (node (ref "J1") (pin "2") (pinfunction "2_2") (pintype "passive"))
      (node (ref "L1") (pin "1") (pinfunction "1_1") (pintype "passive"))
      (node (ref "L2") (pin "1") (pinfunction "1_1") (pintype "passive"))
      (node (ref "L3") (pin "1") (pinfunction "1_1") (pintype "passive"))
      (node (ref "R25") (pin "2") (pinfunction "2_2") (pintype "passive"))
      (node (ref "TP2") (pin "1") (pinfunction "1_1") (pintype "passive"))
      (node (ref "U4") (pin "1") (pinfunction "Vin_1") (pintype "power_in"))
      (node (ref "U4") (pin "3") (pinfunction "EN_3") (pintype "power_in"))
    )
    (net (code "3") (name "/LaserChoice_0") (class "Default")
      (node (ref "TP4") (pin "1") (pinfunction "1_1") (pintype "passive"))
      (node (ref "U1") (pin "1") (pinfunction "1A_1") (pintype "passive"))
      (node (ref "U2") (pin "1") (pinfunction "1A_1") (pintype "passive"))
      (node (ref "U3") (pin "4") (pinfunction "Q_4") (pintype "passive"))
      (node (ref "U6") (pin "1") (pinfunction "A0_1") (pintype "passive"))
      (node (ref "U6") (pin "13") (pinfunction "A2_13") (pintype "passive"))
    )
    (net (code "4") (name "/LaserChoice_1") (class "Default")
      (node (ref "TP5") (pin "1") (pinfunction "1_1") (pintype "passive"))
      (node (ref "U1") (pin "3") (pinfunction "2А_3") (pintype "passive"))
      (node (ref "U2") (pin "3") (pinfunction "2А_3") (pintype "passive"))
      (node (ref "U5") (pin "4") (pinfunction "Q_4") (pintype "passive"))
      (node (ref "U6") (pin "2") (pinfunction "B0_2") (pintype "passive"))
      (node (ref "U6") (pin "5") (pinfunction "B1_5") (pintype "passive"))
    )
    (net (code "5") (name "/MOSFET_1") (class "Default")
      (node (ref "D3") (pin "2") (pinfunction "2_2") (pintype "passive"))
      (node (ref "Q1") (pin "3") (pinfunction "Gate_3") (pintype "passive"))
      (node (ref "Q3") (pin "3") (pinfunction "3_3") (pintype "passive"))
      (node (ref "R5") (pin "1") (pinfunction "1_1") (pintype "passive"))
    )
    (net (code "6") (name "/MOSFET_2") (class "Default")
      (node (ref "D4") (pin "2") (pinfunction "2_2") (pintype "passive"))
      (node (ref "Q1") (pin "1") (pinfunction "Gate_1") (pintype "passive"))
      (node (ref "Q4") (pin "3") (pinfunction "3_3") (pintype "passive"))
      (node (ref "R7") (pin "1") (pinfunction "1_1") (pintype "passive"))
    )
    (net (code "7") (name "/MOSFET_3") (class "Default")
      (node (ref "D5") (pin "2") (pinfunction "2_2") (pintype "passive"))
      (node (ref "Q2") (pin "1") (pinfunction "Gate_1") (pintype "passive"))
      (node (ref "Q5") (pin "3") (pinfunction "3_3") (pintype "passive"))
      (node (ref "R11") (pin "1") (pinfunction "1_1") (pintype "passive"))
    )
    (net (code "8") (name "/MOSFET_4") (class "Default")
      (node (ref "D6") (pin "2") (pinfunction "2_2") (pintype "passive"))
      (node (ref "Q2") (pin "3") (pinfunction "Gate_3") (pintype "passive"))
      (node (ref "Q6") (pin "3") (pinfunction "3_3") (pintype "passive"))
      (node (ref "R13") (pin "1") (pinfunction "1_1") (pintype "passive"))
    )
    (net (code "9") (name "/Shunt_Sens") (class "Default")
      (node (ref "C1") (pin "2") (pinfunction "2_2") (pintype "passive"))
      (node (ref "C10") (pin "2") (pinfunction "2_2") (pintype "passive"))
      (node (ref "C11") (pin "2") (pinfunction "2_2") (pintype "passive"))
      (node (ref "C12") (pin "2") (pinfunction "2_2") (pintype "passive"))
      (node (ref "C13") (pin "2") (pinfunction "2_2") (pintype "passive"))
      (node (ref "C14") (pin "2") (pinfunction "2_2") (pintype "passive"))
      (node (ref "C15") (pin "2") (pinfunction "2_2") (pintype "passive"))
      (node (ref "C16") (pin "2") (pinfunction "2_2") (pintype "passive"))
      (node (ref "C17") (pin "2") (pinfunction "2_2") (pintype "passive"))
      (node (ref "C18") (pin "2") (pinfunction "2_2") (pintype "passive"))
      (node (ref "C19") (pin "2") (pinfunction "2_2") (pintype "passive"))
      (node (ref "C2") (pin "2") (pinfunction "2_2") (pintype "passive"))
      (node (ref "C20") (pin "2") (pinfunction "2_2") (pintype "passive"))
      (node (ref "C3") (pin "2") (pinfunction "2_2") (pintype "passive"))
      (node (ref "C4") (pin "2") (pinfunction "2_2") (pintype "passive"))
      (node (ref "C5") (pin "2") (pinfunction "2_2") (pintype "passive"))
      (node (ref "C6") (pin "2") (pinfunction "2_2") (pintype "passive"))
      (node (ref "C7") (pin "2") (pinfunction "2_2") (pintype "passive"))
      (node (ref "C8") (pin "2") (pinfunction "2_2") (pintype "passive"))
      (node (ref "C9") (pin "2") (pinfunction "2_2") (pintype "passive"))
      (node (ref "R18") (pin "1") (pinfunction "1_1") (pintype "passive"))
      (node (ref "R19") (pin "2") (pinfunction "2_2") (pintype "passive"))
      (node (ref "R20") (pin "2") (pinfunction "2_2") (pintype "passive"))
      (node (ref "R21") (pin "2") (pinfunction "2_2") (pintype "passive"))
      (node (ref "R22") (pin "2") (pinfunction "2_2") (pintype "passive"))
      (node (ref "R23") (pin "2") (pinfunction "2_2") (pintype "passive"))
    )
    (net (code "10") (name "/Start_Sig") (class "Default")
      (node (ref "J1") (pin "3") (pinfunction "3_3") (pintype "passive"))
      (node (ref "TP3") (pin "1") (pinfunction "1_1") (pintype "passive"))
      (node (ref "U3") (pin "1") (pinfunction "CLK_1") (pintype "passive"))
      (node (ref "U5") (pin "1") (pinfunction "CLK_1") (pintype "passive"))
      (node (ref "U7") (pin "3") (pinfunction "IN+_3") (pintype "input"))
    )
    (net (code "11") (name "/VCC_Drain") (class "Default")
      (node (ref "Q1") (pin "4") (pinfunction "Drain_4") (pintype "passive"))
      (node (ref "Q1") (pin "6") (pinfunction "Drain_6") (pintype "passive"))
      (node (ref "Q2") (pin "4") (pinfunction "Drain_4") (pintype "passive"))
      (node (ref "Q2") (pin "6") (pinfunction "Drain_6") (pintype "passive"))
      (node (ref "R1") (pin "2") (pinfunction "2_2") (pintype "passive"))
      (node (ref "R2") (pin "2") (pinfunction "2_2") (pintype "passive"))
      (node (ref "R3") (pin "2") (pinfunction "2_2") (pintype "passive"))
      (node (ref "R4") (pin "2") (pinfunction "2_2") (pintype "passive"))
    )
    (net (code "12") (name "GND") (class "Default")
      (node (ref "C21") (pin "2") (pinfunction "2_2") (pintype "passive"))
      (node (ref "C22") (pin "1") (pinfunction "1_1") (pintype "passive"))
      (node (ref "C23") (pin "1") (pinfunction "1_1") (pintype "passive"))
      (node (ref "C24") (pin "2") (pinfunction "2_2") (pintype "passive"))
      (node (ref "C25") (pin "2") (pinfunction "2_2") (pintype "passive"))
      (node (ref "C26") (pin "1") (pinfunction "1_1") (pintype "passive"))
      (node (ref "C27") (pin "1") (pinfunction "1_1") (pintype "passive"))
      (node (ref "C28") (pin "1") (pinfunction "1_1") (pintype "passive"))
      (node (ref "C29") (pin "2") (pinfunction "2_2") (pintype "passive"))
      (node (ref "C30") (pin "1") (pinfunction "1_1") (pintype "passive"))
      (node (ref "C31") (pin "1") (pinfunction "1_1") (pintype "passive"))
      (node (ref "C32") (pin "1") (pinfunction "1_1") (pintype "passive"))
      (node (ref "C33") (pin "1") (pinfunction "1_1") (pintype "passive"))
      (node (ref "D3") (pin "1") (pinfunction "1_1") (pintype "passive"))
      (node (ref "D4") (pin "1") (pinfunction "1_1") (pintype "passive"))
      (node (ref "D5") (pin "1") (pinfunction "1_1") (pintype "passive"))
      (node (ref "D6") (pin "1") (pinfunction "1_1") (pintype "passive"))
      (node (ref "J1") (pin "6") (pinfunction "6_6") (pintype "passive"))
      (node (ref "J1") (pin "Sh") (pinfunction "A_Sh") (pintype "passive"))
      (node (ref "J2") (pin "A") (pinfunction "GND_A") (pintype "passive"))
      (node (ref "Q3") (pin "2") (pinfunction "2_2") (pintype "passive"))
      (node (ref "Q4") (pin "2") (pinfunction "2_2") (pintype "passive"))
      (node (ref "Q5") (pin "2") (pinfunction "2_2") (pintype "passive"))
      (node (ref "Q6") (pin "2") (pinfunction "2_2") (pintype "passive"))
      (node (ref "Q7") (pin "4") (pinfunction "Source_4") (pintype "passive"))
      (node (ref "R15") (pin "1") (pinfunction "1_1") (pintype "passive"))
      (node (ref "R16") (pin "1") (pinfunction "1_1") (pintype "passive"))
      (node (ref "R19") (pin "1") (pinfunction "1_1") (pintype "passive"))
      (node (ref "R20") (pin "1") (pinfunction "1_1") (pintype "passive"))
      (node (ref "R21") (pin "1") (pinfunction "1_1") (pintype "passive"))
      (node (ref "R22") (pin "1") (pinfunction "1_1") (pintype "passive"))
      (node (ref "R23") (pin "1") (pinfunction "1_1") (pintype "passive"))
      (node (ref "R26") (pin "1") (pinfunction "1_1") (pintype "passive"))
      (node (ref "R8") (pin "1") (pinfunction "1_1") (pintype "passive"))
      (node (ref "R9") (pin "1") (pinfunction "1_1") (pintype "passive"))
      (node (ref "U1") (pin "2") (pinfunction "GND_2") (pintype "power_in"))
      (node (ref "U2") (pin "2") (pinfunction "GND_2") (pintype "power_in"))
      (node (ref "U3") (pin "2") (pinfunction "GND_2") (pintype "power_in"))
      (node (ref "U4") (pin "2") (pinfunction "GND_2") (pintype "power_in"))
      (node (ref "U5") (pin "2") (pinfunction "GND_2") (pintype "power_in"))
      (node (ref "U6") (pin "7") (pinfunction "GND_7") (pintype "power_in"))
      (node (ref "U7") (pin "2") (pinfunction "VCC-_2") (pintype "power_in"))
      (node (ref "U8") (pin "2") (pinfunction "GND_2") (pintype "power_in"))
      (node (ref "U9") (pin "B1") (pinfunction "GND_B1") (pintype "power_in"))
    )
    (net (code "13") (name "Net-(D1-Anode_ch1)") (class "Default")
      (node (ref "C1") (pin "1") (pinfunction "1_1") (pintype "passive"))
      (node (ref "C2") (pin "1") (pinfunction "1_1") (pintype "passive"))
      (node (ref "C3") (pin "1") (pinfunction "1_1") (pintype "passive"))
      (node (ref "C4") (pin "1") (pinfunction "1_1") (pintype "passive"))
      (node (ref "C5") (pin "1") (pinfunction "1_1") (pintype "passive"))
      (node (ref "D1") (pin "1") (pinfunction "Anode_ch1_1") (pintype "power_in"))
      (node (ref "Q1") (pin "2") (pinfunction "Source_2") (pintype "passive"))
      (node (ref "R15") (pin "2") (pinfunction "2_2") (pintype "passive"))
      (node (ref "TP8") (pin "1") (pinfunction "1_1") (pintype "passive"))
    )
    (net (code "14") (name "Net-(D1-Anode_ch2)") (class "Default")
      (node (ref "C10") (pin "1") (pinfunction "1_1") (pintype "passive"))
      (node (ref "C6") (pin "1") (pinfunction "1_1") (pintype "passive"))
      (node (ref "C7") (pin "1") (pinfunction "1_1") (pintype "passive"))
      (node (ref "C8") (pin "1") (pinfunction "1_1") (pintype "passive"))
      (node (ref "C9") (pin "1") (pinfunction "1_1") (pintype "passive"))
      (node (ref "D1") (pin "2") (pinfunction "Anode_ch2_2") (pintype "power_in"))
      (node (ref "Q1") (pin "5") (pinfunction "Source_5") (pintype "passive"))
      (node (ref "R8") (pin "2") (pinfunction "2_2") (pintype "passive"))
      (node (ref "TP6") (pin "1") (pinfunction "1_1") (pintype "passive"))
    )
    (net (code "15") (name "Net-(D1-Anode_ch3)") (class "Default")
      (node (ref "C11") (pin "1") (pinfunction "1_1") (pintype "passive"))
      (node (ref "C12") (pin "1") (pinfunction "1_1") (pintype "passive"))
      (node (ref "C13") (pin "1") (pinfunction "1_1") (pintype "passive"))
      (node (ref "C14") (pin "1") (pinfunction "1_1") (pintype "passive"))
      (node (ref "C15") (pin "1") (pinfunction "1_1") (pintype "passive"))
      (node (ref "D1") (pin "3") (pinfunction "Anode_ch3_3") (pintype "power_in"))
      (node (ref "Q2") (pin "5") (pinfunction "Source_5") (pintype "passive"))
      (node (ref "R9") (pin "2") (pinfunction "2_2") (pintype "passive"))
      (node (ref "TP7") (pin "1") (pinfunction "1_1") (pintype "passive"))
    )
    (net (code "16") (name "Net-(D1-Anode_ch4)") (class "Default")
      (node (ref "C16") (pin "1") (pinfunction "1_1") (pintype "passive"))
      (node (ref "C17") (pin "1") (pinfunction "1_1") (pintype "passive"))
      (node (ref "C18") (pin "1") (pinfunction "1_1") (pintype "passive"))
      (node (ref "C19") (pin "1") (pinfunction "1_1") (pintype "passive"))
      (node (ref "C20") (pin "1") (pinfunction "1_1") (pintype "passive"))
      (node (ref "D1") (pin "4") (pinfunction "Anode_ch4_4") (pintype "power_in"))
      (node (ref "Q2") (pin "2") (pinfunction "Source_2") (pintype "passive"))
      (node (ref "R16") (pin "2") (pinfunction "2_2") (pintype "passive"))
      (node (ref "TP9") (pin "1") (pinfunction "1_1") (pintype "passive"))
    )
    (net (code "17") (name "Net-(D1-Cathode)") (class "Default")
      (node (ref "D1") (pin "5") (pinfunction "Cathode_5") (pintype "power_in"))
      (node (ref "D2") (pin "1") (pinfunction "1_1") (pintype "passive"))
      (node (ref "Q7") (pin "3") (pinfunction "Drain_3") (pintype "passive"))
    )
    (net (code "18") (name "Net-(J2-Antenna)") (class "Default")
      (node (ref "J2") (pin "1") (pinfunction "Antenna_1") (pintype "passive"))
      (node (ref "R18") (pin "2") (pinfunction "2_2") (pintype "passive"))
    )
    (net (code "19") (name "Net-(Q3-Pad1)") (class "Default")
      (node (ref "Q3") (pin "1") (pinfunction "1_1") (pintype "passive"))
      (node (ref "R6") (pin "2") (pinfunction "2_2") (pintype "passive"))
    )
    (net (code "20") (name "Net-(Q4-Pad1)") (class "Default")
      (node (ref "Q4") (pin "1") (pinfunction "1_1") (pintype "passive"))
      (node (ref "R10") (pin "2") (pinfunction "2_2") (pintype "passive"))
    )
    (net (code "21") (name "Net-(Q5-Pad1)") (class "Default")
      (node (ref "Q5") (pin "1") (pinfunction "1_1") (pintype "passive"))
      (node (ref "R12") (pin "2") (pinfunction "2_2") (pintype "passive"))
    )
    (net (code "22") (name "Net-(Q6-Pad1)") (class "Default")
      (node (ref "Q6") (pin "1") (pinfunction "1_1") (pintype "passive"))
      (node (ref "R14") (pin "2") (pinfunction "2_2") (pintype "passive"))
    )
    (net (code "23") (name "Net-(Q7-Gate)") (class "Default")
      (node (ref "Q7") (pin "1") (pinfunction "Gate_1") (pintype "passive"))
      (node (ref "U9") (pin "A2") (pinfunction "OutH_A2") (pintype "power_in"))
      (node (ref "U9") (pin "B2") (pinfunction "OutL_B2") (pintype "power_in"))
    )
    (net (code "24") (name "Net-(U1A-1Y)") (class "Default")
      (node (ref "U1") (pin "6") (pinfunction "1Y_6") (pintype "passive"))
      (node (ref "U6") (pin "4") (pinfunction "A1_4") (pintype "passive"))
    )
    (net (code "25") (name "Net-(U1B-2Y)") (class "Default")
      (node (ref "U1") (pin "4") (pinfunction "2Y_4") (pintype "passive"))
      (node (ref "U6") (pin "12") (pinfunction "B2_12") (pintype "passive"))
    )
    (net (code "26") (name "Net-(U2A-1Y)") (class "Default")
      (node (ref "U2") (pin "6") (pinfunction "1Y_6") (pintype "passive"))
      (node (ref "U6") (pin "10") (pinfunction "A3_10") (pintype "passive"))
    )
    (net (code "27") (name "Net-(U2B-2Y)") (class "Default")
      (node (ref "U2") (pin "4") (pinfunction "2Y_4") (pintype "passive"))
      (node (ref "U6") (pin "9") (pinfunction "B3_9") (pintype "passive"))
    )
    (net (code "28") (name "Net-(U3-D)") (class "Default")
      (node (ref "J1") (pin "4") (pinfunction "4_4") (pintype "passive"))
      (node (ref "U3") (pin "3") (pinfunction "D_3") (pintype "passive"))
    )
    (net (code "29") (name "Net-(U5-D)") (class "Default")
      (node (ref "J1") (pin "5") (pinfunction "5_5") (pintype "passive"))
      (node (ref "U5") (pin "3") (pinfunction "D_3") (pintype "passive"))
    )
    (net (code "30") (name "Net-(U6A-~{O}0)") (class "Default")
      (node (ref "R6") (pin "1") (pinfunction "1_1") (pintype "passive"))
      (node (ref "U6") (pin "3") (pinfunction "~{O}0_3") (pintype "passive"))
    )
    (net (code "31") (name "Net-(U6B-~{O}1)") (class "Default")
      (node (ref "R10") (pin "1") (pinfunction "1_1") (pintype "passive"))
      (node (ref "U6") (pin "6") (pinfunction "~{O}1_6") (pintype "passive"))
    )
    (net (code "32") (name "Net-(U6C-~{O}2)") (class "Default")
      (node (ref "R12") (pin "1") (pinfunction "1_1") (pintype "passive"))
      (node (ref "U6") (pin "11") (pinfunction "~{O}2_11") (pintype "passive"))
    )
    (net (code "33") (name "Net-(U6D-~{O}3)") (class "Default")
      (node (ref "R14") (pin "1") (pinfunction "1_1") (pintype "passive"))
      (node (ref "U6") (pin "8") (pinfunction "~{O}3_8") (pintype "passive"))
    )
    (net (code "34") (name "Net-(U7-IN-)") (class "Default")
      (node (ref "R25") (pin "1") (pinfunction "1_1") (pintype "passive"))
      (node (ref "R26") (pin "2") (pinfunction "2_2") (pintype "passive"))
      (node (ref "U7") (pin "4") (pinfunction "IN-_4") (pintype "input"))
    )
    (net (code "35") (name "Net-(U7-OUTPUT)") (class "Default")
      (node (ref "R17") (pin "1") (pinfunction "1_1") (pintype "passive"))
      (node (ref "R24") (pin "1") (pinfunction "1_1") (pintype "passive"))
      (node (ref "U7") (pin "1") (pinfunction "OUTPUT_1") (pintype "output"))
    )
    (net (code "36") (name "Net-(U7-VCC+)") (class "Default")
      (node (ref "C27") (pin "2") (pinfunction "2_2") (pintype "passive"))
      (node (ref "L2") (pin "2") (pinfunction "2_2") (pintype "passive"))
      (node (ref "U7") (pin "5") (pinfunction "VCC+_5") (pintype "power_in"))
    )
    (net (code "37") (name "Net-(U8-A1)") (class "Default")
      (node (ref "C29") (pin "1") (pinfunction "1_1") (pintype "passive"))
      (node (ref "R17") (pin "2") (pinfunction "2_2") (pintype "passive"))
      (node (ref "U8") (pin "1") (pinfunction "A1_1") (pintype "input"))
    )
    (net (code "38") (name "Net-(U8-A2)") (class "Default")
      (node (ref "C30") (pin "2") (pinfunction "2_2") (pintype "passive"))
      (node (ref "R24") (pin "2") (pinfunction "2_2") (pintype "passive"))
      (node (ref "U8") (pin "3") (pinfunction "A2_3") (pintype "input"))
    )
    (net (code "39") (name "Net-(U8-VCC)") (class "Default")
      (node (ref "C31") (pin "2") (pinfunction "2_2") (pintype "passive"))
      (node (ref "L3") (pin "2") (pinfunction "2_2") (pintype "passive"))
      (node (ref "U8") (pin "5") (pinfunction "VCC_5") (pintype "power_in"))
    )
    (net (code "40") (name "Net-(U8-Y1)") (class "Default")
      (node (ref "U8") (pin "6") (pinfunction "Y1_6") (pintype "output"))
      (node (ref "U9") (pin "C1") (pinfunction "IN+_C1") (pintype "input"))
    )
    (net (code "41") (name "Net-(U8-Y2)") (class "Default")
      (node (ref "U8") (pin "4") (pinfunction "Y2_4") (pintype "output"))
      (node (ref "U9") (pin "C2") (pinfunction "IN-_C2") (pintype "input"))
    )
    (net (code "42") (name "Net-(U9-VDD)") (class "Default")
      (node (ref "C26") (pin "2") (pinfunction "2_2") (pintype "passive"))
      (node (ref "C28") (pin "2") (pinfunction "2_2") (pintype "passive"))
      (node (ref "L1") (pin "2") (pinfunction "2_2") (pintype "passive"))
      (node (ref "U9") (pin "A1") (pinfunction "VDD_A1") (pintype "power_in"))
    )
    (net (code "43") (name "VCC") (class "Default")
      (node (ref "D2") (pin "2") (pinfunction "2_2") (pintype "passive"))
      (node (ref "J1") (pin "1") (pinfunction "1_1") (pintype "passive"))
      (node (ref "R1") (pin "1") (pinfunction "1_1") (pintype "passive"))
      (node (ref "R11") (pin "2") (pinfunction "2_2") (pintype "passive"))
      (node (ref "R13") (pin "2") (pinfunction "2_2") (pintype "passive"))
      (node (ref "R2") (pin "1") (pinfunction "1_1") (pintype "passive"))
      (node (ref "R3") (pin "1") (pinfunction "1_1") (pintype "passive"))
      (node (ref "R4") (pin "1") (pinfunction "1_1") (pintype "passive"))
      (node (ref "R5") (pin "2") (pinfunction "2_2") (pintype "passive"))
      (node (ref "R7") (pin "2") (pinfunction "2_2") (pintype "passive"))
      (node (ref "TP1") (pin "1") (pinfunction "1_1") (pintype "passive"))
    )
  )
)
